# Isolator.net
KiCad netlist of a schematic drawn in Altium Designer
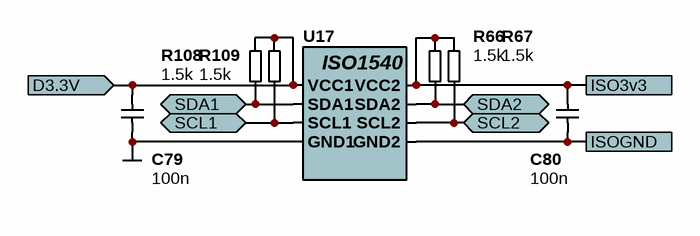
[diagram p0: Isolator.SchDoc]

(export (version "E")
  (design (tool "Eeschema 10.0.6"))
  (components
    (comp (ref "C79")
      (value "100n")
      (footprint "0402-Capacitor")
      (description "Capacitor 0402")
      (fields (field (name "TOLERANCE") "±20%"))
      (libsource (lib "PRL_PDC") (part "C_0402"))
    )
    (comp (ref "C80")
      (value "100n")
      (footprint "0402-Capacitor")
      (description "Capacitor 0402")
      (fields (field (name "TOLERANCE") "±20%"))
      (libsource (lib "PRL_PDC") (part "C_0402"))
    )
    (comp (ref "R66")
      (value "1.5k")
      (footprint "0603-RESISTOR")
      (description "Resistor 0603")
      (fields (field (name "TOLERANCE") "±1%"))
      (libsource (lib "PRL_PDC") (part "R_0603"))
    )
    (comp (ref "R67")
      (value "1.5k")
      (footprint "0603-RESISTOR")
      (description "Resistor 0603")
      (fields (field (name "TOLERANCE") "±1%"))
      (libsource (lib "PRL_PDC") (part "R_0603"))
    )
    (comp (ref "R108")
      (value "1.5k")
      (footprint "0603-RESISTOR")
      (description "Resistor 0603")
      (fields (field (name "TOLERANCE") "±1%"))
      (libsource (lib "PRL_PDC") (part "R_0603"))
    )
    (comp (ref "R109")
      (value "1.5k")
      (footprint "0603-RESISTOR")
      (description "Resistor 0603")
      (fields (field (name "TOLERANCE") "±1%"))
      (libsource (lib "PRL_PDC") (part "R_0603"))
    )
    (comp (ref "U17") (value "ISO1540DR") (footprint "SOIC8") (libsource (lib "PRL_PDC") (part "ISO1540DR")))
  )
  (nets
    (net (code "1") (name "/D3.3V") (class "Default")
      (node (ref "C79") (pin "2") (pinfunction "2_2") (pintype "passive"))
      (node (ref "R108") (pin "1") (pinfunction "1_1") (pintype "passive"))
      (node (ref "R109") (pin "1") (pinfunction "1_1") (pintype "passive"))
      (node (ref "U17") (pin "1") (pinfunction "VCC1_1") (pintype "passive"))
    )
    (net (code "2") (name "/ISO3v3") (class "Default")
      (node (ref "C80") (pin "2") (pinfunction "2_2") (pintype "passive"))
      (node (ref "R66") (pin "1") (pinfunction "1_1") (pintype "passive"))
      (node (ref "R67") (pin "1") (pinfunction "1_1") (pintype "passive"))
      (node (ref "U17") (pin "8") (pinfunction "VCC2_8") (pintype "passive"))
    )
    (net (code "3") (name "/ISOGND") (class "Default")
      (node (ref "C80") (pin "1") (pinfunction "1_1") (pintype "passive"))
      (node (ref "U17") (pin "5") (pinfunction "GND2_5") (pintype "passive"))
    )
    (net (code "4") (name "/SCL1") (class "Default")
      (node (ref "R109") (pin "2") (pinfunction "2_2") (pintype "passive"))
      (node (ref "U17") (pin "3") (pinfunction "SCL1_3") (pintype "passive"))
    )
    (net (code "5") (name "/SCL2") (class "Default")
      (node (ref "R67") (pin "2") (pinfunction "2_2") (pintype "passive"))
      (node (ref "U17") (pin "6") (pinfunction "SCL2_6") (pintype "passive"))
    )
    (net (code "6") (name "/SDA1") (class "Default")
      (node (ref "R108") (pin "2") (pinfunction "2_2") (pintype "passive"))
      (node (ref "U17") (pin "2") (pinfunction "SDA1_2") (pintype "passive"))
    )
    (net (code "7") (name "/SDA2") (class "Default")
      (node (ref "R66") (pin "2") (pinfunction "2_2") (pintype "passive"))
      (node (ref "U17") (pin "7") (pinfunction "SDA2_7") (pintype "passive"))
    )
    (net (code "8") (name "DGND") (class "Default")
      (node (ref "C79") (pin "1") (pinfunction "1_1") (pintype "passive"))
      (node (ref "U17") (pin "4") (pinfunction "GND1_4") (pintype "passive"))
    )
  )
)
